# Board-Back.net
KiCad netlist of a schematic drawn in EAGLE
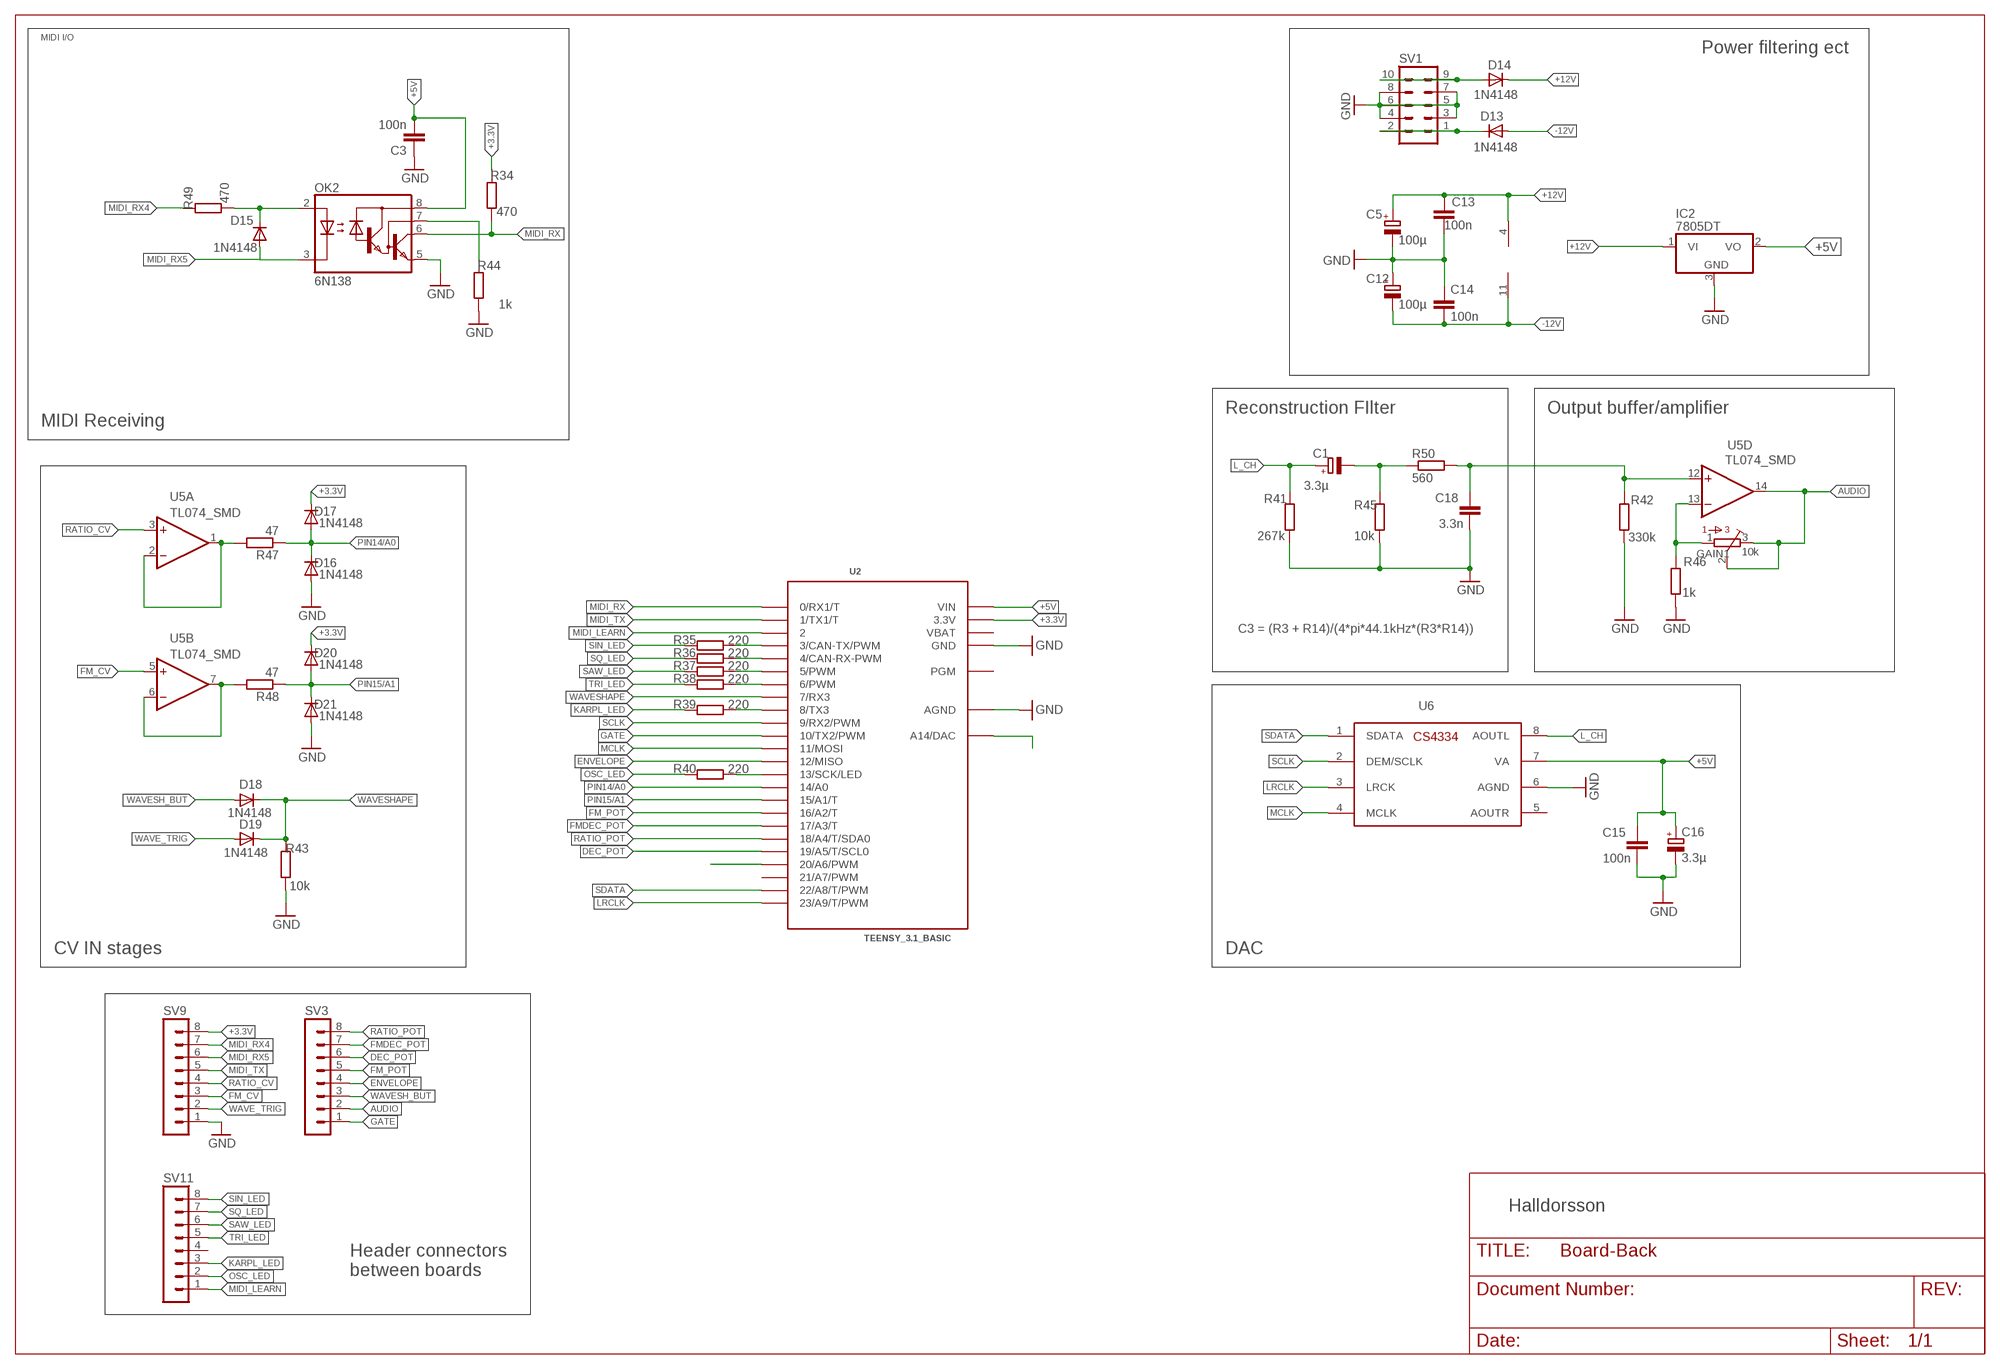
[diagram p0: schematic, sheet 1]

(export (version "E")
  (design (tool "Eeschema 10.0.6"))
  (components
    (comp (ref "C1")
      (value "3.3µ")
      (footprint "eagle-import:153CLV-0405")
      (libsource (lib "eagle-import") (part "CPOL-EU153CLV-0405"))
    )
    (comp (ref "C3")
      (value "100n")
      (footprint "eagle-import:C1206")
      (libsource (lib "eagle-import") (part "C-EUC1206"))
    )
    (comp (ref "C5")
      (value "100µ")
      (footprint "eagle-import:E5-6")
      (libsource (lib "eagle-import") (part "CPOL-EUE5-6"))
    )
    (comp (ref "C12")
      (value "100µ")
      (footprint "eagle-import:E5-6")
      (libsource (lib "eagle-import") (part "CPOL-EUE5-6"))
    )
    (comp (ref "C13")
      (value "100n")
      (footprint "eagle-import:C1206")
      (libsource (lib "eagle-import") (part "C-EUC1206"))
    )
    (comp (ref "C14")
      (value "100n")
      (footprint "eagle-import:C1206")
      (libsource (lib "eagle-import") (part "C-EUC1206"))
    )
    (comp (ref "C15")
      (value "100n")
      (footprint "eagle-import:C1206")
      (libsource (lib "eagle-import") (part "C-EUC1206"))
    )
    (comp (ref "C16")
      (value "3.3µ")
      (footprint "eagle-import:153CLV-0505")
      (libsource (lib "eagle-import") (part "CPOL-EU153CLV-0505"))
    )
    (comp (ref "C18")
      (value "3.3n")
      (footprint "eagle-import:C1206")
      (libsource (lib "eagle-import") (part "C-EUC1206"))
    )
    (comp (ref "D13")
      (value "1N4148")
      (footprint "eagle-import:DO35-7")
      (libsource (lib "eagle-import") (part "1N4148DO35-7"))
    )
    (comp (ref "D14")
      (value "1N4148")
      (footprint "eagle-import:DO35-7")
      (libsource (lib "eagle-import") (part "1N4148DO35-7"))
    )
    (comp (ref "D15")
      (value "1N4148")
      (footprint "eagle-import:DO35-7")
      (libsource (lib "eagle-import") (part "1N4148DO35-7"))
    )
    (comp (ref "D16")
      (value "1N4148")
      (footprint "eagle-import:DO35-7")
      (libsource (lib "eagle-import") (part "1N4148DO35-7"))
    )
    (comp (ref "D17")
      (value "1N4148")
      (footprint "eagle-import:DO35-7")
      (libsource (lib "eagle-import") (part "1N4148DO35-7"))
    )
    (comp (ref "D18")
      (value "1N4148")
      (footprint "eagle-import:DO35-7")
      (libsource (lib "eagle-import") (part "1N4148DO35-7"))
    )
    (comp (ref "D19")
      (value "1N4148")
      (footprint "eagle-import:DO35-7")
      (libsource (lib "eagle-import") (part "1N4148DO35-7"))
    )
    (comp (ref "D20")
      (value "1N4148")
      (footprint "eagle-import:DO35-7")
      (libsource (lib "eagle-import") (part "1N4148DO35-7"))
    )
    (comp (ref "D21")
      (value "1N4148")
      (footprint "eagle-import:DO35-7")
      (libsource (lib "eagle-import") (part "1N4148DO35-7"))
    )
    (comp (ref "GAIN1")
      (value "10k")
      (footprint "eagle-import:BOURNS_3362P_TRIMMER")
      (libsource (lib "eagle-import") (part "BOURNS_3362P_TRIMMERP"))
    )
    (comp (ref "IC2")
      (value "7805DT")
      (footprint "eagle-import:TO252")
      (libsource (lib "eagle-import") (part "78DT05"))
    )
    (comp (ref "OK2")
      (value "6N138")
      (footprint "eagle-import:DIL08")
      (fields (field (name "MF") "VISHAY/TELEFUNKEN"))
      (libsource (lib "eagle-import") (part "6N138"))
    )
    (comp (ref "R34")
      (value "470")
      (footprint "eagle-import:M1206")
      (libsource (lib "eagle-import") (part "R-EU_M1206"))
    )
    (comp (ref "R35")
      (value "220")
      (footprint "eagle-import:M1206")
      (libsource (lib "eagle-import") (part "R-EU_M1206"))
    )
    (comp (ref "R36")
      (value "220")
      (footprint "eagle-import:M1206")
      (libsource (lib "eagle-import") (part "R-EU_M1206"))
    )
    (comp (ref "R37")
      (value "220")
      (footprint "eagle-import:M1206")
      (libsource (lib "eagle-import") (part "R-EU_M1206"))
    )
    (comp (ref "R38")
      (value "220")
      (footprint "eagle-import:M1206")
      (libsource (lib "eagle-import") (part "R-EU_M1206"))
    )
    (comp (ref "R39")
      (value "220")
      (footprint "eagle-import:M1206")
      (libsource (lib "eagle-import") (part "R-EU_M1206"))
    )
    (comp (ref "R40")
      (value "220")
      (footprint "eagle-import:M1206")
      (libsource (lib "eagle-import") (part "R-EU_M1206"))
    )
    (comp (ref "R41")
      (value "267k")
      (footprint "eagle-import:M1206")
      (libsource (lib "eagle-import") (part "R-EU_M1206"))
    )
    (comp (ref "R42")
      (value "330k")
      (footprint "eagle-import:M1206")
      (libsource (lib "eagle-import") (part "R-EU_M1206"))
    )
    (comp (ref "R43")
      (value "10k")
      (footprint "eagle-import:M1206")
      (libsource (lib "eagle-import") (part "R-EU_M1206"))
    )
    (comp (ref "R44")
      (value "1k")
      (footprint "eagle-import:M1206")
      (libsource (lib "eagle-import") (part "R-EU_M1206"))
    )
    (comp (ref "R45")
      (value "10k")
      (footprint "eagle-import:M1206")
      (libsource (lib "eagle-import") (part "R-EU_M1206"))
    )
    (comp (ref "R46")
      (value "1k")
      (footprint "eagle-import:M1206")
      (libsource (lib "eagle-import") (part "R-EU_M1206"))
    )
    (comp (ref "R47")
      (value "47")
      (footprint "eagle-import:M1206")
      (libsource (lib "eagle-import") (part "R-EU_M1206"))
    )
    (comp (ref "R48")
      (value "47")
      (footprint "eagle-import:M1206")
      (libsource (lib "eagle-import") (part "R-EU_M1206"))
    )
    (comp (ref "R49")
      (value "470")
      (footprint "eagle-import:M1206")
      (libsource (lib "eagle-import") (part "R-EU_M1206"))
    )
    (comp (ref "R50")
      (value "560")
      (footprint "eagle-import:M1206")
      (libsource (lib "eagle-import") (part "R-EU_M1206"))
    )
    (comp (ref "SV1")
      (value "10PIN_BACKSIDE")
      (footprint "eagle-import:10PIN_BACKSIDE")
      (libsource (lib "eagle-import") (part "10PIN_BACKSIDE"))
    )
    (comp (ref "SV3")
      (value "MA08-1")
      (footprint "eagle-import:MA08-1")
      (libsource (lib "eagle-import") (part "MA08-1"))
    )
    (comp (ref "SV9")
      (value "MA08-1")
      (footprint "eagle-import:MA08-1")
      (libsource (lib "eagle-import") (part "MA08-1"))
    )
    (comp (ref "SV11")
      (value "MA08-1")
      (footprint "eagle-import:MA08-1")
      (libsource (lib "eagle-import") (part "MA08-1"))
    )
    (comp (ref "U2")
      (value "TEENSY_3.1_BASIC")
      (footprint "eagle-import:TEENSY_3.1_BASIC")
      (libsource (lib "eagle-import") (part "TEENSY_3.1_BASIC"))
    )
    (comp (ref "U5")
      (value "TL074_SMD")
      (footprint "eagle-import:SO14")
      (libsource (lib "eagle-import") (part "TL074_SMD"))
    )
    (comp (ref "U6")
      (value "CS4334")
      (footprint "eagle-import:SOIC127P600X175-8N")
      (libsource (lib "eagle-import") (part "CS4334"))
    )
  )
  (nets
    (net (code "1") (name "+3.3V") (class "Default")
      (node (ref "D17") (pin "C") (pinfunction "C_C") (pintype "passive"))
      (node (ref "D20") (pin "C") (pinfunction "C_C") (pintype "passive"))
      (node (ref "R34") (pin "2") (pinfunction "2_2") (pintype "passive"))
      (node (ref "SV9") (pin "8") (pinfunction "8_8") (pintype "passive"))
      (node (ref "U2") (pin "3.3V") (pinfunction "3.3V_3.3V") (pintype "power_in"))
      (node (ref "U2") (pin "3.3V1") (pinfunction "3.3V_3.3V1") (pintype "power_in"))
    )
    (net (code "2") (name "+5V") (class "Default")
      (node (ref "C15") (pin "1") (pinfunction "1_1") (pintype "passive"))
      (node (ref "C16") (pin "+") (pinfunction "+_+") (pintype "passive"))
      (node (ref "C3") (pin "2") (pinfunction "2_2") (pintype "passive"))
      (node (ref "IC2") (pin "2") (pinfunction "VO_2") (pintype "passive"))
      (node (ref "OK2") (pin "8") (pinfunction "VCC_8") (pintype "passive"))
      (node (ref "U2") (pin "VIN") (pinfunction "VIN_VIN") (pintype "power_in"))
      (node (ref "U6") (pin "7") (pinfunction "VA_7") (pintype "bidirectional"))
    )
    (net (code "3") (name "+12V") (class "Default")
      (node (ref "C13") (pin "1") (pinfunction "1_1") (pintype "passive"))
      (node (ref "C5") (pin "+") (pinfunction "+_+") (pintype "passive"))
      (node (ref "D14") (pin "C") (pinfunction "C_C") (pintype "passive"))
      (node (ref "IC2") (pin "1") (pinfunction "VI_1") (pintype "input"))
      (node (ref "U5") (pin "4") (pinfunction "V+_4") (pintype "power_in"))
    )
    (net (code "4") (name "-12V") (class "Default")
      (node (ref "C12") (pin "-") (pinfunction "-_-") (pintype "passive"))
      (node (ref "C14") (pin "2") (pinfunction "2_2") (pintype "passive"))
      (node (ref "D13") (pin "A") (pinfunction "A_A") (pintype "passive"))
      (node (ref "U5") (pin "11") (pinfunction "V-_11") (pintype "power_in"))
    )
    (net (code "5") (name "/VBAT") (class "Default")
      (node (ref "U2") (pin "VBAT") (pinfunction "VBAT_VBAT") (pintype "power_in"))
    )
    (net (code "6") (name "AUDIO") (class "Default")
      (node (ref "GAIN1") (pin "2") (pinfunction "2_2") (pintype "passive"))
      (node (ref "GAIN1") (pin "3") (pinfunction "3_3") (pintype "passive"))
      (node (ref "SV3") (pin "2") (pinfunction "2_2") (pintype "passive"))
      (node (ref "U5") (pin "14") (pinfunction "OUT_14") (pintype "output"))
    )
    (net (code "7") (name "DEC_POT") (class "Default")
      (node (ref "SV3") (pin "6") (pinfunction "6_6") (pintype "passive"))
      (node (ref "U2") (pin "19/A5") (pinfunction "19/A5/T/SCL0_19/A5") (pintype "bidirectional"))
    )
    (net (code "8") (name "ENVELOPE") (class "Default")
      (node (ref "SV3") (pin "4") (pinfunction "4_4") (pintype "passive"))
      (node (ref "U2") (pin "12") (pinfunction "12/MISO_12") (pintype "bidirectional"))
    )
    (net (code "9") (name "FMDEC_POT") (class "Default")
      (node (ref "SV3") (pin "7") (pinfunction "7_7") (pintype "passive"))
      (node (ref "U2") (pin "17/A3") (pinfunction "17/A3/T_17/A3") (pintype "bidirectional"))
    )
    (net (code "10") (name "FM_CV") (class "Default")
      (node (ref "SV9") (pin "3") (pinfunction "3_3") (pintype "passive"))
      (node (ref "U5") (pin "5") (pinfunction "+IN_5") (pintype "input"))
    )
    (net (code "11") (name "FM_POT") (class "Default")
      (node (ref "SV3") (pin "5") (pinfunction "5_5") (pintype "passive"))
      (node (ref "U2") (pin "16/A2") (pinfunction "16/A2/T_16/A2") (pintype "bidirectional"))
    )
    (net (code "12") (name "GATE") (class "Default")
      (node (ref "SV3") (pin "1") (pinfunction "1_1") (pintype "passive"))
      (node (ref "U2") (pin "10") (pinfunction "10/TX2/PWM_10") (pintype "bidirectional"))
    )
    (net (code "13") (name "GND") (class "Default")
      (node (ref "C12") (pin "+") (pinfunction "+_+") (pintype "passive"))
      (node (ref "C13") (pin "2") (pinfunction "2_2") (pintype "passive"))
      (node (ref "C14") (pin "1") (pinfunction "1_1") (pintype "passive"))
      (node (ref "C15") (pin "2") (pinfunction "2_2") (pintype "passive"))
      (node (ref "C16") (pin "-") (pinfunction "-_-") (pintype "passive"))
      (node (ref "C18") (pin "2") (pinfunction "2_2") (pintype "passive"))
      (node (ref "C3") (pin "1") (pinfunction "1_1") (pintype "passive"))
      (node (ref "C5") (pin "-") (pinfunction "-_-") (pintype "passive"))
      (node (ref "D16") (pin "A") (pinfunction "A_A") (pintype "passive"))
      (node (ref "D21") (pin "A") (pinfunction "A_A") (pintype "passive"))
      (node (ref "IC2") (pin "3") (pinfunction "GND_3") (pintype "passive"))
      (node (ref "OK2") (pin "5") (pinfunction "GND_5") (pintype "passive"))
      (node (ref "R41") (pin "2") (pinfunction "2_2") (pintype "passive"))
      (node (ref "R42") (pin "2") (pinfunction "2_2") (pintype "passive"))
      (node (ref "R43") (pin "1") (pinfunction "1_1") (pintype "passive"))
      (node (ref "R44") (pin "1") (pinfunction "1_1") (pintype "passive"))
      (node (ref "R45") (pin "2") (pinfunction "2_2") (pintype "passive"))
      (node (ref "R46") (pin "2") (pinfunction "2_2") (pintype "passive"))
      (node (ref "SV1") (pin "3") (pinfunction "3_3") (pintype "passive"))
      (node (ref "SV1") (pin "4") (pinfunction "4_4") (pintype "passive"))
      (node (ref "SV1") (pin "5") (pinfunction "5_5") (pintype "passive"))
      (node (ref "SV1") (pin "6") (pinfunction "6_6") (pintype "passive"))
      (node (ref "SV1") (pin "7") (pinfunction "7_7") (pintype "passive"))
      (node (ref "SV1") (pin "8") (pinfunction "8_8") (pintype "passive"))
      (node (ref "SV9") (pin "1") (pinfunction "1_1") (pintype "passive"))
      (node (ref "U2") (pin "AGND") (pinfunction "AGND_AGND") (pintype "power_in"))
      (node (ref "U2") (pin "GND") (pinfunction "GND_GND") (pintype "power_in"))
      (node (ref "U2") (pin "GND1") (pinfunction "GND_GND1") (pintype "power_in"))
      (node (ref "U6") (pin "6") (pinfunction "AGND_6") (pintype "bidirectional"))
    )
    (net (code "14") (name "KARPL_LED") (class "Default")
      (node (ref "R39") (pin "2") (pinfunction "2_2") (pintype "passive"))
      (node (ref "SV11") (pin "3") (pinfunction "3_3") (pintype "passive"))
    )
    (net (code "15") (name "LRCLK") (class "Default")
      (node (ref "U2") (pin "23/A9") (pinfunction "23/A9/T/PWM_23/A9") (pintype "bidirectional"))
      (node (ref "U6") (pin "3") (pinfunction "LRCK_3") (pintype "bidirectional"))
    )
    (net (code "16") (name "L_CH") (class "Default")
      (node (ref "C1") (pin "+") (pinfunction "+_+") (pintype "passive"))
      (node (ref "R41") (pin "1") (pinfunction "1_1") (pintype "passive"))
      (node (ref "U6") (pin "8") (pinfunction "AOUTL_8") (pintype "bidirectional"))
    )
    (net (code "17") (name "MCLK") (class "Default")
      (node (ref "U2") (pin "11") (pinfunction "11/MOSI_11") (pintype "bidirectional"))
      (node (ref "U6") (pin "4") (pinfunction "MCLK_4") (pintype "bidirectional"))
    )
    (net (code "18") (name "MIDI_LEARN") (class "Default")
      (node (ref "SV11") (pin "1") (pinfunction "1_1") (pintype "passive"))
      (node (ref "U2") (pin "2") (pinfunction "2_2") (pintype "bidirectional"))
    )
    (net (code "19") (name "MIDI_RX") (class "Default")
      (node (ref "OK2") (pin "6") (pinfunction "VO_6") (pintype "passive"))
      (node (ref "R34") (pin "1") (pinfunction "1_1") (pintype "passive"))
      (node (ref "U2") (pin "0") (pinfunction "0/RX1/T_0") (pintype "bidirectional"))
    )
    (net (code "20") (name "MIDI_RX4") (class "Default")
      (node (ref "R49") (pin "2") (pinfunction "2_2") (pintype "passive"))
      (node (ref "SV9") (pin "7") (pinfunction "7_7") (pintype "passive"))
    )
    (net (code "21") (name "MIDI_RX5") (class "Default")
      (node (ref "D15") (pin "A") (pinfunction "A_A") (pintype "passive"))
      (node (ref "OK2") (pin "3") (pinfunction "C_3") (pintype "passive"))
      (node (ref "SV9") (pin "6") (pinfunction "6_6") (pintype "passive"))
    )
    (net (code "22") (name "MIDI_TX") (class "Default")
      (node (ref "SV9") (pin "5") (pinfunction "5_5") (pintype "passive"))
      (node (ref "U2") (pin "1") (pinfunction "1/TX1/T_1") (pintype "bidirectional"))
    )
    (net (code "23") (name "Net-(C1-Pad-)") (class "Default")
      (node (ref "C1") (pin "-") (pinfunction "-_-") (pintype "passive"))
      (node (ref "R45") (pin "1") (pinfunction "1_1") (pintype "passive"))
      (node (ref "R50") (pin "1") (pinfunction "1_1") (pintype "passive"))
    )
    (net (code "24") (name "Net-(D13-PadC)") (class "Default")
      (node (ref "D13") (pin "C") (pinfunction "C_C") (pintype "passive"))
      (node (ref "SV1") (pin "1") (pinfunction "1_1") (pintype "passive"))
      (node (ref "SV1") (pin "2") (pinfunction "2_2") (pintype "passive"))
    )
    (net (code "25") (name "Net-(D14-PadA)") (class "Default")
      (node (ref "D14") (pin "A") (pinfunction "A_A") (pintype "passive"))
      (node (ref "SV1") (pin "10") (pinfunction "10_10") (pintype "passive"))
      (node (ref "SV1") (pin "9") (pinfunction "9_9") (pintype "passive"))
    )
    (net (code "26") (name "Net-(OK2-A)") (class "Default")
      (node (ref "D15") (pin "C") (pinfunction "C_C") (pintype "passive"))
      (node (ref "OK2") (pin "2") (pinfunction "A_2") (pintype "passive"))
      (node (ref "R49") (pin "1") (pinfunction "1_1") (pintype "passive"))
    )
    (net (code "27") (name "Net-(OK2-VB)") (class "Default")
      (node (ref "OK2") (pin "7") (pinfunction "VB_7") (pintype "passive"))
      (node (ref "R44") (pin "2") (pinfunction "2_2") (pintype "passive"))
    )
    (net (code "28") (name "Net-(U2-3{slash}CAN-TX{slash}PWM)") (class "Default")
      (node (ref "R35") (pin "1") (pinfunction "1_1") (pintype "passive"))
      (node (ref "U2") (pin "3") (pinfunction "3/CAN-TX/PWM_3") (pintype "bidirectional"))
    )
    (net (code "29") (name "Net-(U2-4{slash}CAN-RX-PWM)") (class "Default")
      (node (ref "R36") (pin "1") (pinfunction "1_1") (pintype "passive"))
      (node (ref "U2") (pin "4") (pinfunction "4/CAN-RX-PWM_4") (pintype "bidirectional"))
    )
    (net (code "30") (name "Net-(U2-5{slash}PWM)") (class "Default")
      (node (ref "R37") (pin "1") (pinfunction "1_1") (pintype "passive"))
      (node (ref "U2") (pin "5") (pinfunction "5/PWM_5") (pintype "bidirectional"))
    )
    (net (code "31") (name "Net-(U2-6{slash}PWM)") (class "Default")
      (node (ref "R38") (pin "1") (pinfunction "1_1") (pintype "passive"))
      (node (ref "U2") (pin "6") (pinfunction "6/PWM_6") (pintype "bidirectional"))
    )
    (net (code "32") (name "Net-(U2-8{slash}TX3)") (class "Default")
      (node (ref "R39") (pin "1") (pinfunction "1_1") (pintype "passive"))
      (node (ref "U2") (pin "8") (pinfunction "8/TX3_8") (pintype "bidirectional"))
    )
    (net (code "33") (name "Net-(U2-13{slash}SCK{slash}LED)") (class "Default")
      (node (ref "R40") (pin "1") (pinfunction "1_1") (pintype "passive"))
      (node (ref "U2") (pin "13") (pinfunction "13/SCK/LED_13") (pintype "bidirectional"))
    )
    (net (code "34") (name "Net-(U5A--IN)") (class "Default")
      (node (ref "R47") (pin "2") (pinfunction "2_2") (pintype "passive"))
      (node (ref "U5") (pin "1") (pinfunction "OUT_1") (pintype "output"))
      (node (ref "U5") (pin "2") (pinfunction "-IN_2") (pintype "input"))
    )
    (net (code "35") (name "Net-(U5B--IN)") (class "Default")
      (node (ref "R48") (pin "2") (pinfunction "2_2") (pintype "passive"))
      (node (ref "U5") (pin "6") (pinfunction "-IN_6") (pintype "input"))
      (node (ref "U5") (pin "7") (pinfunction "OUT_7") (pintype "output"))
    )
    (net (code "36") (name "Net-(U5D-+IN)") (class "Default")
      (node (ref "C18") (pin "1") (pinfunction "1_1") (pintype "passive"))
      (node (ref "R42") (pin "1") (pinfunction "1_1") (pintype "passive"))
      (node (ref "R50") (pin "2") (pinfunction "2_2") (pintype "passive"))
      (node (ref "U5") (pin "12") (pinfunction "+IN_12") (pintype "input"))
    )
    (net (code "37") (name "Net-(U5D--IN)") (class "Default")
      (node (ref "GAIN1") (pin "1") (pinfunction "1_1") (pintype "passive"))
      (node (ref "R46") (pin "1") (pinfunction "1_1") (pintype "passive"))
      (node (ref "U5") (pin "13") (pinfunction "-IN_13") (pintype "input"))
    )
    (net (code "38") (name "OSC_LED") (class "Default")
      (node (ref "R40") (pin "2") (pinfunction "2_2") (pintype "passive"))
      (node (ref "SV11") (pin "2") (pinfunction "2_2") (pintype "passive"))
    )
    (net (code "39") (name "PIN14{slash}A0") (class "Default")
      (node (ref "D16") (pin "C") (pinfunction "C_C") (pintype "passive"))
      (node (ref "D17") (pin "A") (pinfunction "A_A") (pintype "passive"))
      (node (ref "R47") (pin "1") (pinfunction "1_1") (pintype "passive"))
      (node (ref "U2") (pin "14/A0") (pinfunction "14/A0_14/A0") (pintype "bidirectional"))
    )
    (net (code "40") (name "PIN15{slash}A1") (class "Default")
      (node (ref "D20") (pin "A") (pinfunction "A_A") (pintype "passive"))
      (node (ref "D21") (pin "C") (pinfunction "C_C") (pintype "passive"))
      (node (ref "R48") (pin "1") (pinfunction "1_1") (pintype "passive"))
      (node (ref "U2") (pin "15/A1") (pinfunction "15/A1/T_15/A1") (pintype "bidirectional"))
    )
    (net (code "41") (name "RATIO_CV") (class "Default")
      (node (ref "SV9") (pin "4") (pinfunction "4_4") (pintype "passive"))
      (node (ref "U5") (pin "3") (pinfunction "+IN_3") (pintype "input"))
    )
    (net (code "42") (name "RATIO_POT") (class "Default")
      (node (ref "SV3") (pin "8") (pinfunction "8_8") (pintype "passive"))
      (node (ref "U2") (pin "18/A4") (pinfunction "18/A4/T/SDA0_18/A4") (pintype "bidirectional"))
    )
    (net (code "43") (name "SAW_LED") (class "Default")
      (node (ref "R37") (pin "2") (pinfunction "2_2") (pintype "passive"))
      (node (ref "SV11") (pin "6") (pinfunction "6_6") (pintype "passive"))
    )
    (net (code "44") (name "SCLK") (class "Default")
      (node (ref "U2") (pin "9") (pinfunction "9/RX2/PWM_9") (pintype "bidirectional"))
      (node (ref "U6") (pin "2") (pinfunction "DEM/SCLK_2") (pintype "bidirectional"))
    )
    (net (code "45") (name "SDATA") (class "Default")
      (node (ref "U2") (pin "22/A8") (pinfunction "22/A8/T/PWM_22/A8") (pintype "bidirectional"))
      (node (ref "U6") (pin "1") (pinfunction "SDATA_1") (pintype "bidirectional"))
    )
    (net (code "46") (name "SIN_LED") (class "Default")
      (node (ref "R35") (pin "2") (pinfunction "2_2") (pintype "passive"))
      (node (ref "SV11") (pin "8") (pinfunction "8_8") (pintype "passive"))
    )
    (net (code "47") (name "SQ_LED") (class "Default")
      (node (ref "R36") (pin "2") (pinfunction "2_2") (pintype "passive"))
      (node (ref "SV11") (pin "7") (pinfunction "7_7") (pintype "passive"))
    )
    (net (code "48") (name "TRI_LED") (class "Default")
      (node (ref "R38") (pin "2") (pinfunction "2_2") (pintype "passive"))
      (node (ref "SV11") (pin "5") (pinfunction "5_5") (pintype "passive"))
    )
    (net (code "49") (name "WAVESHAPE") (class "Default")
      (node (ref "D18") (pin "C") (pinfunction "C_C") (pintype "passive"))
      (node (ref "D19") (pin "C") (pinfunction "C_C") (pintype "passive"))
      (node (ref "R43") (pin "2") (pinfunction "2_2") (pintype "passive"))
      (node (ref "U2") (pin "7") (pinfunction "7/RX3_7") (pintype "bidirectional"))
    )
    (net (code "50") (name "WAVESH_BUT") (class "Default")
      (node (ref "D18") (pin "A") (pinfunction "A_A") (pintype "passive"))
      (node (ref "SV3") (pin "3") (pinfunction "3_3") (pintype "passive"))
    )
    (net (code "51") (name "WAVE_TRIG") (class "Default")
      (node (ref "D19") (pin "A") (pinfunction "A_A") (pintype "passive"))
      (node (ref "SV9") (pin "2") (pinfunction "2_2") (pintype "passive"))
    )
    (net (code "52") (name "unconnected-(SV11-Pad4)") (class "Default")
      (node (ref "SV11") (pin "4") (pinfunction "4_4") (pintype "passive"))
    )
    (net (code "53") (name "unconnected-(U2-20{slash}A6{slash}PWM-Pad20{slash}A6)") (class "Default")
      (node (ref "U2") (pin "20/A6") (pinfunction "20/A6/PWM_20/A6") (pintype "bidirectional"))
    )
    (net (code "54") (name "unconnected-(U2-21{slash}A7{slash}PWM-Pad21{slash}A7)") (class "Default")
      (node (ref "U2") (pin "21/A7") (pinfunction "21/A7/PWM_21/A7") (pintype "bidirectional"))
    )
    (net (code "55") (name "unconnected-(U2-A14{slash}DAC-PadA14)") (class "Default")
      (node (ref "U2") (pin "A14") (pinfunction "A14/DAC_A14") (pintype "bidirectional"))
    )
    (net (code "56") (name "unconnected-(U2-PadPGM)") (class "Default")
      (node (ref "U2") (pin "PGM") (pinfunction "PGM_PGM") (pintype "bidirectional"))
    )
    (net (code "57") (name "unconnected-(U6-AOUTR-Pad5)") (class "Default")
      (node (ref "U6") (pin "5") (pinfunction "AOUTR_5") (pintype "bidirectional"))
    )
  )
)
